# jinks_01_release.net
KiCad netlist of a schematic drawn in EAGLE
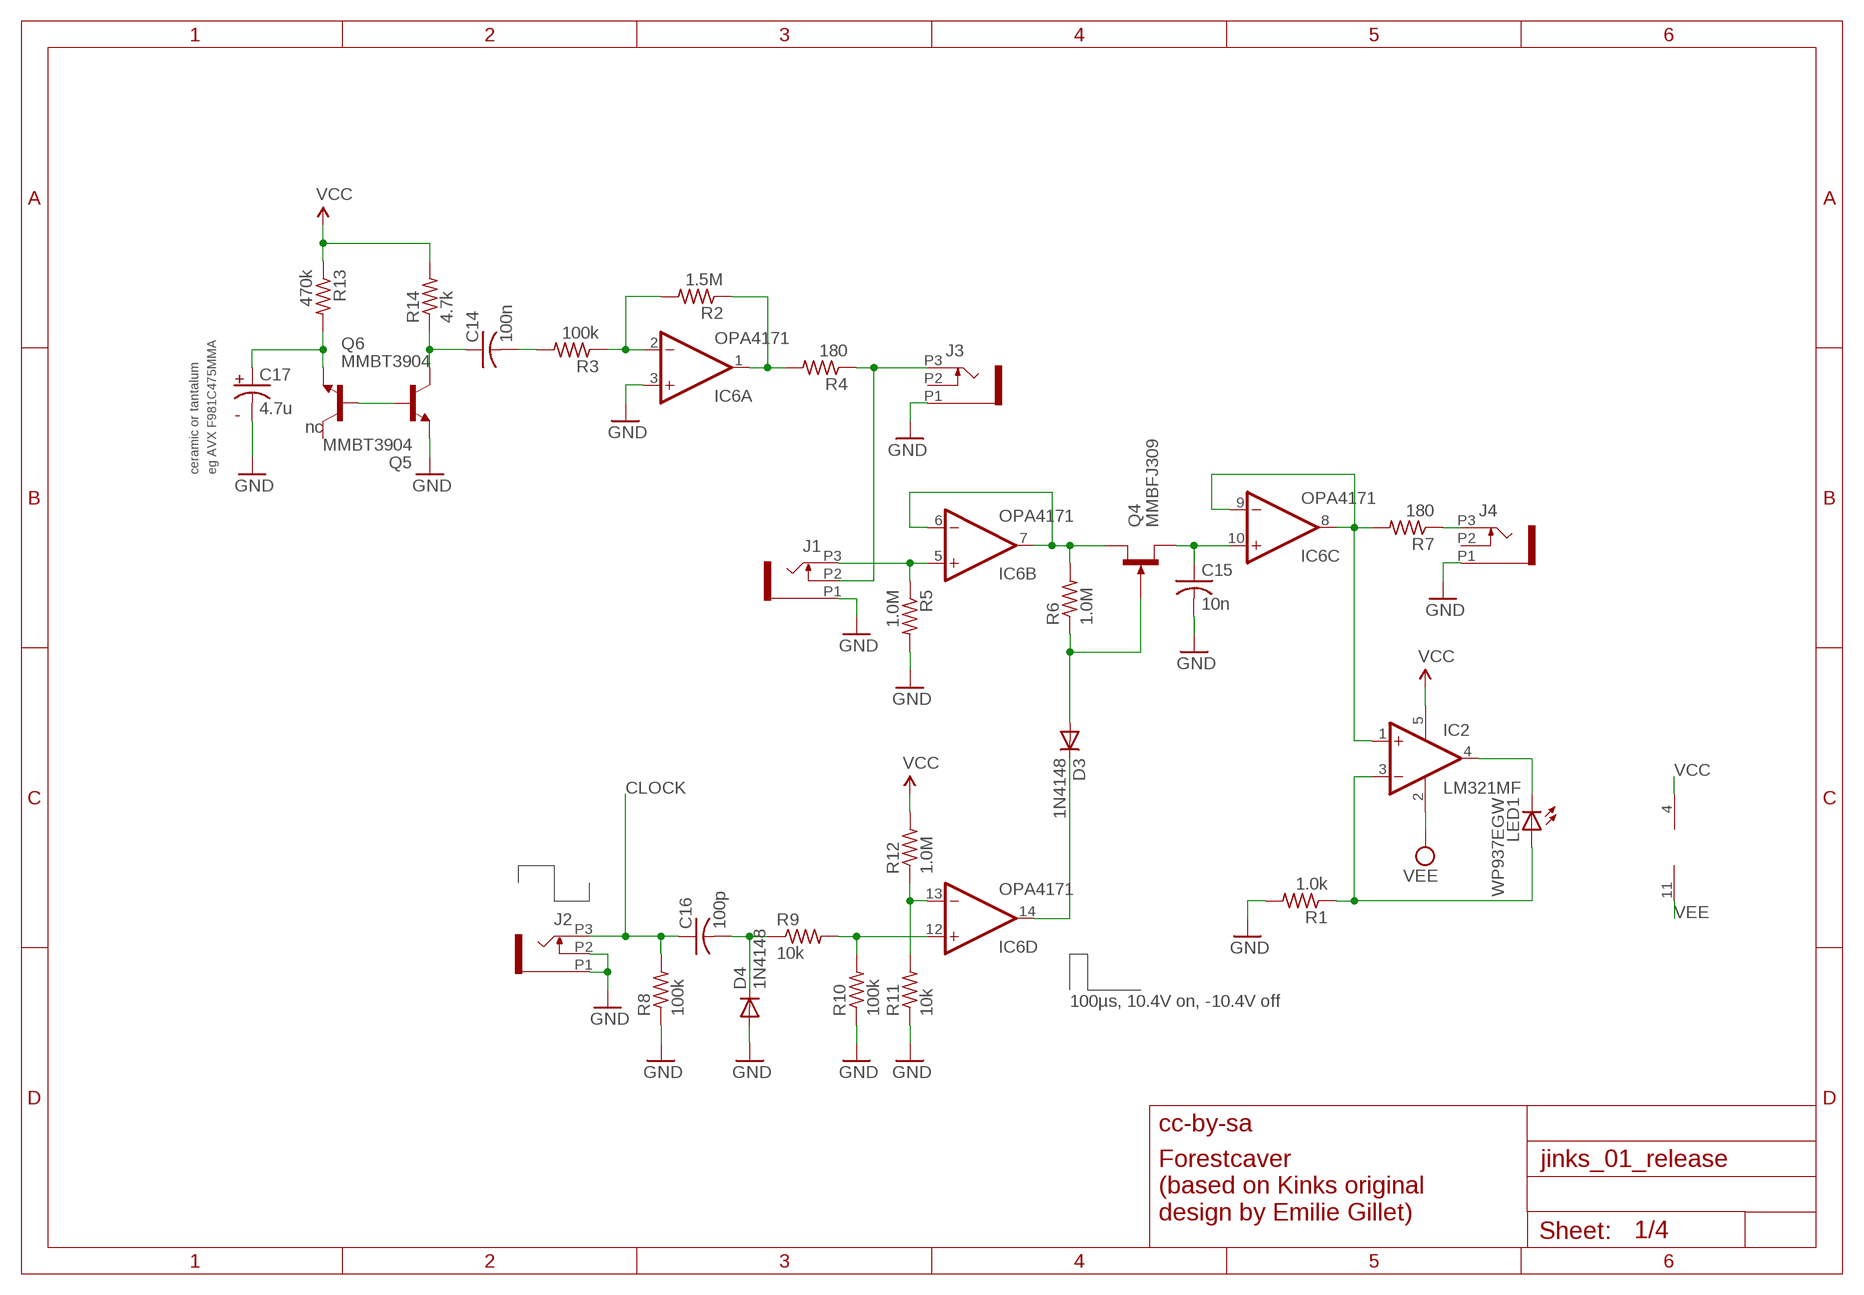
[diagram p0: schematic, sheet 1]
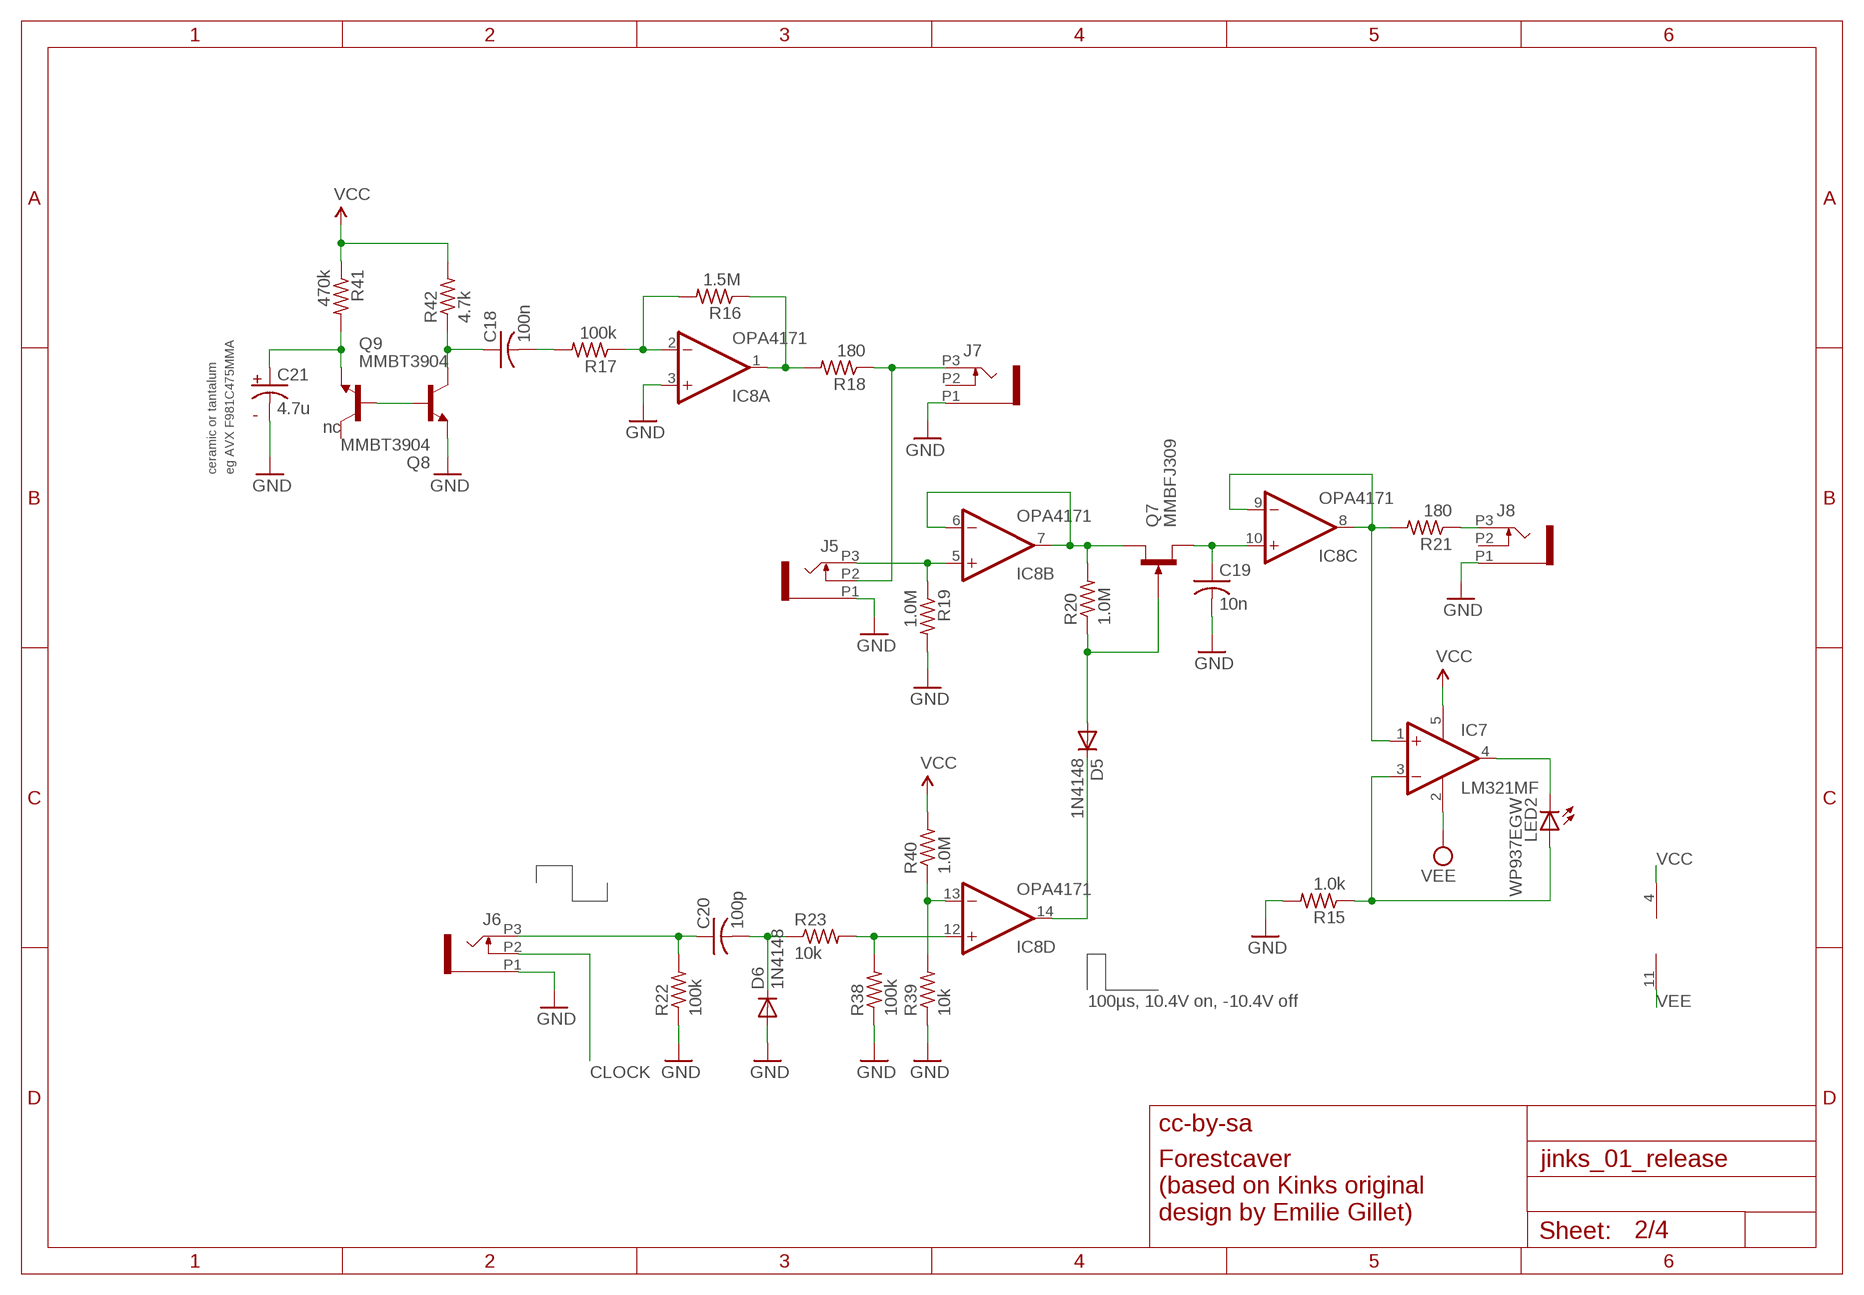
[diagram p1: schematic, sheet 2]
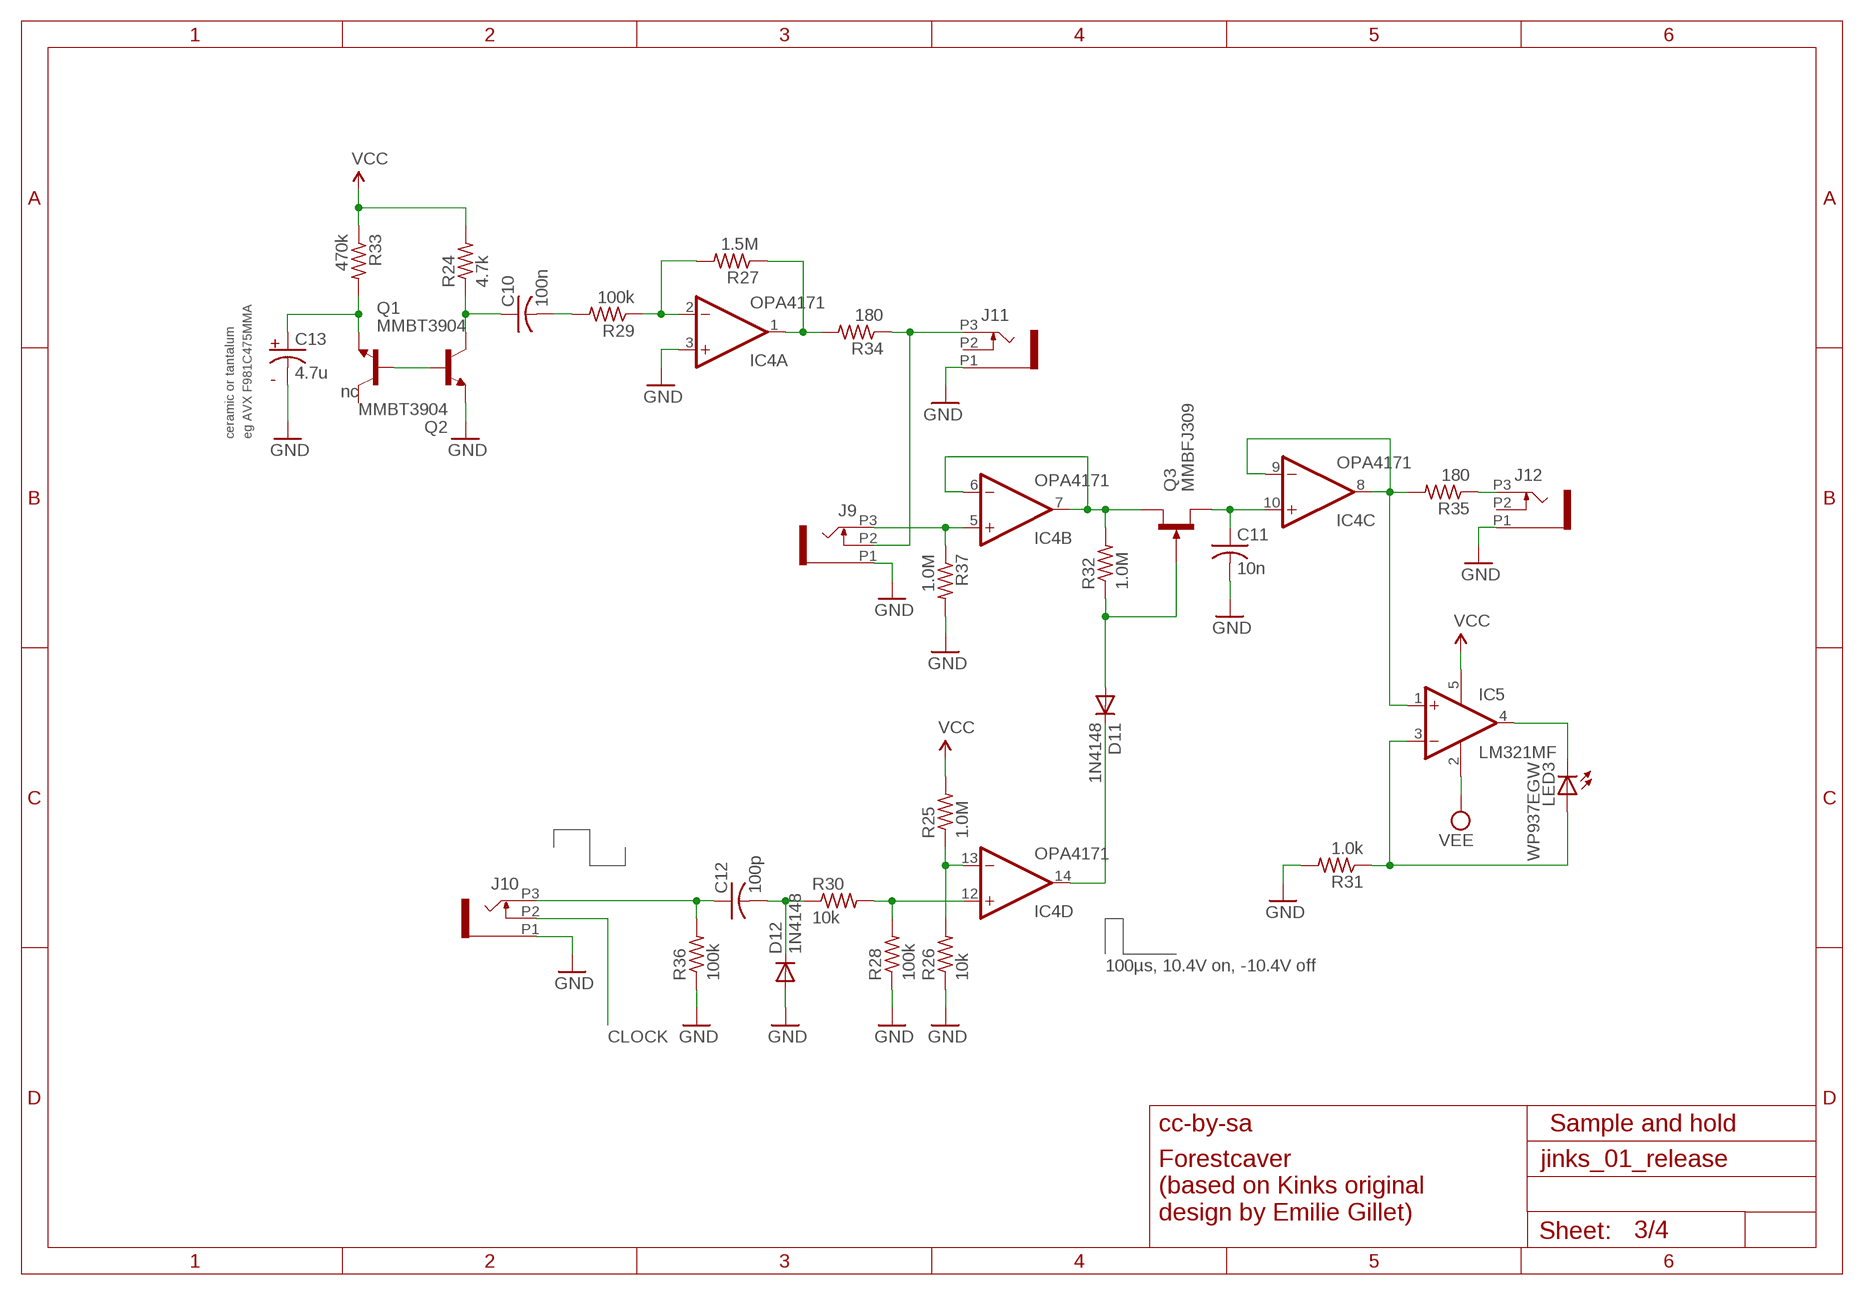
[diagram p2: schematic, sheet 3]
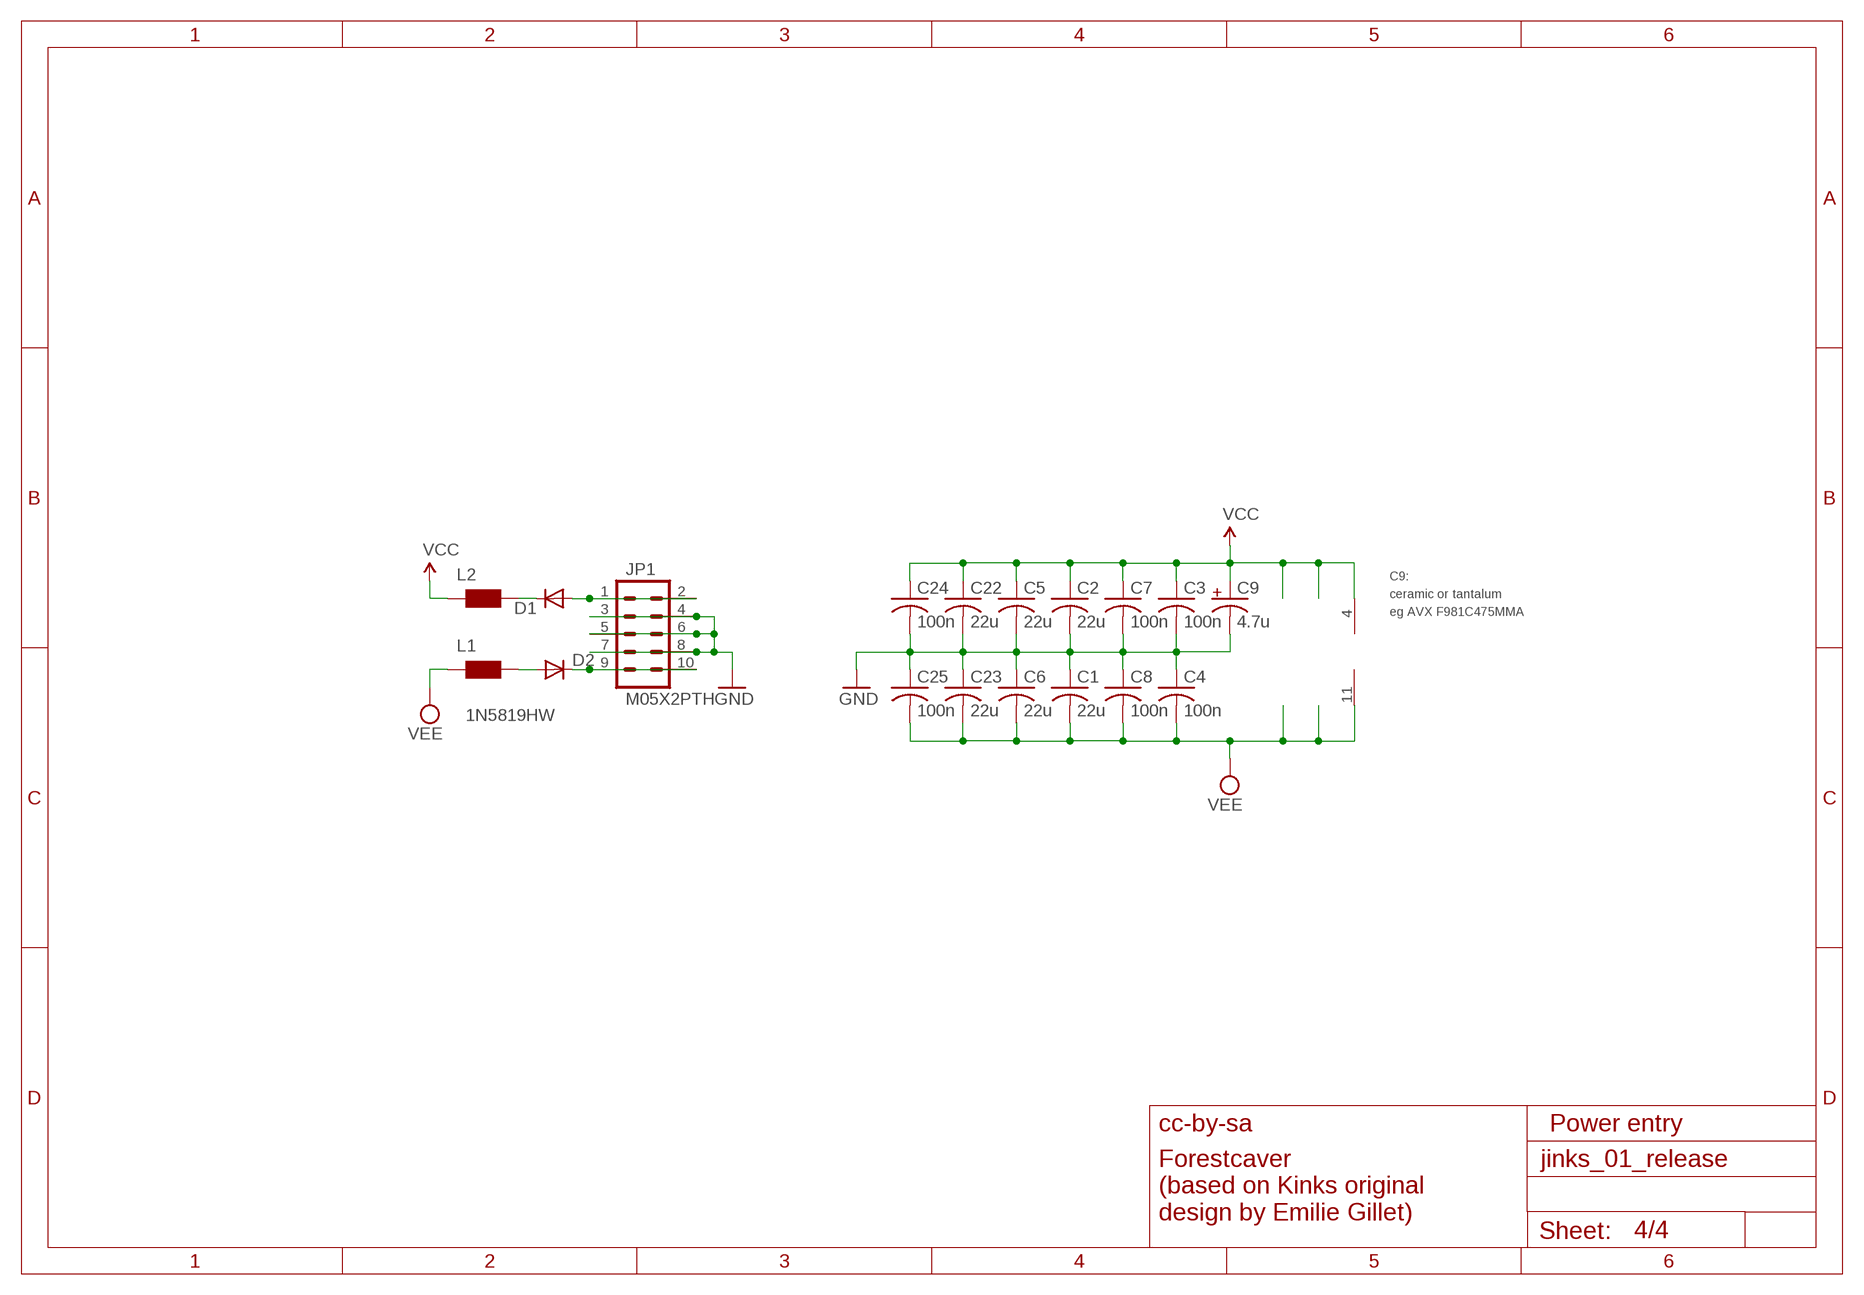
[diagram p3: schematic, sheet 4]

(export (version "E")
  (design (tool "Eeschema 10.0.6"))
  (components
    (comp (ref "C10")
      (value "100n")
      (footprint "eagle-import:C0603")
      (libsource (lib "eagle-import") (part "C-USC0603"))
    )
    (comp (ref "C11")
      (value "10n")
      (footprint "eagle-import:C0603")
      (libsource (lib "eagle-import") (part "C-USC0603"))
    )
    (comp (ref "C12")
      (value "100p")
      (footprint "eagle-import:C0603")
      (libsource (lib "eagle-import") (part "C-USC0603"))
    )
    (comp (ref "C13")
      (value "4.7u")
      (footprint "eagle-import:C0603")
      (libsource (lib "eagle-import") (part "C-USC0603"))
    )
    (comp (ref "D11")
      (value "1N4148")
      (footprint "eagle-import:SOD523")
      (libsource (lib "eagle-import") (part "DIODE-SOD523"))
    )
    (comp (ref "D12")
      (value "1N4148")
      (footprint "eagle-import:SOD523")
      (libsource (lib "eagle-import") (part "DIODE-SOD523"))
    )
    (comp (ref "IC4")
      (value "OPA4171")
      (footprint "eagle-import:TSSOP14")
      (libsource (lib "eagle-import") (part "TL074PW"))
    )
    (comp (ref "IC5")
      (value "LM321MF")
      (footprint "eagle-import:SOT23-5")
      (libsource (lib "eagle-import") (part "LM321?MF"))
    )
    (comp (ref "J9")
      (value "PJ301_THONKICONN6")
      (footprint "eagle-import:WQP_PJ_301M6")
      (libsource (lib "eagle-import") (part "PJ301_THONKICONN6"))
    )
    (comp (ref "J10")
      (value "PJ301_THONKICONN6")
      (footprint "eagle-import:WQP_PJ_301M6")
      (libsource (lib "eagle-import") (part "PJ301_THONKICONN6"))
    )
    (comp (ref "J11")
      (value "PJ301_THONKICONN6")
      (footprint "eagle-import:WQP_PJ_301M6")
      (libsource (lib "eagle-import") (part "PJ301_THONKICONN6"))
    )
    (comp (ref "J12")
      (value "PJ301_THONKICONN6")
      (footprint "eagle-import:WQP_PJ_301M6")
      (libsource (lib "eagle-import") (part "PJ301_THONKICONN6"))
    )
    (comp (ref "LED3")
      (value "WP937EGW")
      (footprint "eagle-import:LED3MM")
      (libsource (lib "eagle-import") (part "LED3MM"))
    )
    (comp (ref "Q1")
      (value "MMBT3904")
      (footprint "eagle-import:SOT23-BEC")
      (libsource (lib "eagle-import") (part "-NPN-SOT23-BECMMBT3904LT1"))
    )
    (comp (ref "Q2")
      (value "MMBT3904")
      (footprint "eagle-import:SOT23-BEC")
      (libsource (lib "eagle-import") (part "-NPN-SOT23-BECMMBT3904LT1"))
    )
    (comp (ref "Q3")
      (value "MMBFJ309")
      (footprint "eagle-import:SOT23")
      (libsource (lib "eagle-import") (part "MMBFJ3"))
    )
    (comp (ref "R24")
      (value "4.7k")
      (footprint "eagle-import:R0603")
      (libsource (lib "eagle-import") (part "R-US_R0603"))
    )
    (comp (ref "R25")
      (value "1.0M")
      (footprint "eagle-import:R0603")
      (libsource (lib "eagle-import") (part "R-US_R0603"))
    )
    (comp (ref "R26")
      (value "10k")
      (footprint "eagle-import:R0603")
      (libsource (lib "eagle-import") (part "R-US_R0603"))
    )
    (comp (ref "R27")
      (value "1.5M")
      (footprint "eagle-import:R0603")
      (libsource (lib "eagle-import") (part "R-US_R0603"))
    )
    (comp (ref "R28")
      (value "100k")
      (footprint "eagle-import:R0603")
      (libsource (lib "eagle-import") (part "R-US_R0603"))
    )
    (comp (ref "R29")
      (value "100k")
      (footprint "eagle-import:R0603")
      (libsource (lib "eagle-import") (part "R-US_R0603"))
    )
    (comp (ref "R30")
      (value "10k")
      (footprint "eagle-import:R0603")
      (libsource (lib "eagle-import") (part "R-US_R0603"))
    )
    (comp (ref "R31")
      (value "1.0k")
      (footprint "eagle-import:R0603")
      (libsource (lib "eagle-import") (part "R-US_R0603"))
    )
    (comp (ref "R32")
      (value "1.0M")
      (footprint "eagle-import:R0603")
      (libsource (lib "eagle-import") (part "R-US_R0603"))
    )
    (comp (ref "R33")
      (value "470k")
      (footprint "eagle-import:R0603")
      (libsource (lib "eagle-import") (part "R-US_R0603"))
    )
    (comp (ref "R34")
      (value "180")
      (footprint "eagle-import:R0603")
      (libsource (lib "eagle-import") (part "R-US_R0603"))
    )
    (comp (ref "R35")
      (value "180")
      (footprint "eagle-import:R0603")
      (libsource (lib "eagle-import") (part "R-US_R0603"))
    )
    (comp (ref "R36")
      (value "100k")
      (footprint "eagle-import:R0603")
      (libsource (lib "eagle-import") (part "R-US_R0603"))
    )
    (comp (ref "R37")
      (value "1.0M")
      (footprint "eagle-import:R0603")
      (libsource (lib "eagle-import") (part "R-US_R0603"))
    )
    (comp (ref "C18")
      (value "100n")
      (footprint "eagle-import:C0603")
      (libsource (lib "eagle-import") (part "C-USC0603"))
    )
    (comp (ref "C19")
      (value "10n")
      (footprint "eagle-import:C0603")
      (libsource (lib "eagle-import") (part "C-USC0603"))
    )
    (comp (ref "C20")
      (value "100p")
      (footprint "eagle-import:C0603")
      (libsource (lib "eagle-import") (part "C-USC0603"))
    )
    (comp (ref "C21")
      (value "4.7u")
      (footprint "eagle-import:C0603")
      (libsource (lib "eagle-import") (part "C-USC0603"))
    )
    (comp (ref "D5")
      (value "1N4148")
      (footprint "eagle-import:SOD523")
      (libsource (lib "eagle-import") (part "DIODE-SOD523"))
    )
    (comp (ref "D6")
      (value "1N4148")
      (footprint "eagle-import:SOD523")
      (libsource (lib "eagle-import") (part "DIODE-SOD523"))
    )
    (comp (ref "IC7")
      (value "LM321MF")
      (footprint "eagle-import:SOT23-5")
      (libsource (lib "eagle-import") (part "LM321?MF"))
    )
    (comp (ref "IC8")
      (value "OPA4171")
      (footprint "eagle-import:TSSOP14")
      (libsource (lib "eagle-import") (part "TL074PW"))
    )
    (comp (ref "J5")
      (value "PJ301_THONKICONN6")
      (footprint "eagle-import:WQP_PJ_301M6")
      (libsource (lib "eagle-import") (part "PJ301_THONKICONN6"))
    )
    (comp (ref "J6")
      (value "PJ301_THONKICONN6")
      (footprint "eagle-import:WQP_PJ_301M6")
      (libsource (lib "eagle-import") (part "PJ301_THONKICONN6"))
    )
    (comp (ref "J7")
      (value "PJ301_THONKICONN6")
      (footprint "eagle-import:WQP_PJ_301M6")
      (libsource (lib "eagle-import") (part "PJ301_THONKICONN6"))
    )
    (comp (ref "J8")
      (value "PJ301_THONKICONN6")
      (footprint "eagle-import:WQP_PJ_301M6")
      (libsource (lib "eagle-import") (part "PJ301_THONKICONN6"))
    )
    (comp (ref "LED2")
      (value "WP937EGW")
      (footprint "eagle-import:LED3MM")
      (libsource (lib "eagle-import") (part "LED3MM"))
    )
    (comp (ref "Q7")
      (value "MMBFJ309")
      (footprint "eagle-import:SOT23")
      (libsource (lib "eagle-import") (part "MMBFJ3"))
    )
    (comp (ref "Q8")
      (value "MMBT3904")
      (footprint "eagle-import:SOT23-BEC")
      (libsource (lib "eagle-import") (part "-NPN-SOT23-BECMMBT3904LT1"))
    )
    (comp (ref "Q9")
      (value "MMBT3904")
      (footprint "eagle-import:SOT23-BEC")
      (libsource (lib "eagle-import") (part "-NPN-SOT23-BECMMBT3904LT1"))
    )
    (comp (ref "R15")
      (value "1.0k")
      (footprint "eagle-import:R0603")
      (libsource (lib "eagle-import") (part "R-US_R0603"))
    )
    (comp (ref "R16")
      (value "1.5M")
      (footprint "eagle-import:R0603")
      (libsource (lib "eagle-import") (part "R-US_R0603"))
    )
    (comp (ref "R17")
      (value "100k")
      (footprint "eagle-import:R0603")
      (libsource (lib "eagle-import") (part "R-US_R0603"))
    )
    (comp (ref "R18")
      (value "180")
      (footprint "eagle-import:R0603")
      (libsource (lib "eagle-import") (part "R-US_R0603"))
    )
    (comp (ref "R19")
      (value "1.0M")
      (footprint "eagle-import:R0603")
      (libsource (lib "eagle-import") (part "R-US_R0603"))
    )
    (comp (ref "R20")
      (value "1.0M")
      (footprint "eagle-import:R0603")
      (libsource (lib "eagle-import") (part "R-US_R0603"))
    )
    (comp (ref "R21")
      (value "180")
      (footprint "eagle-import:R0603")
      (libsource (lib "eagle-import") (part "R-US_R0603"))
    )
    (comp (ref "R22")
      (value "100k")
      (footprint "eagle-import:R0603")
      (libsource (lib "eagle-import") (part "R-US_R0603"))
    )
    (comp (ref "R23")
      (value "10k")
      (footprint "eagle-import:R0603")
      (libsource (lib "eagle-import") (part "R-US_R0603"))
    )
    (comp (ref "R38")
      (value "100k")
      (footprint "eagle-import:R0603")
      (libsource (lib "eagle-import") (part "R-US_R0603"))
    )
    (comp (ref "R39")
      (value "10k")
      (footprint "eagle-import:R0603")
      (libsource (lib "eagle-import") (part "R-US_R0603"))
    )
    (comp (ref "R40")
      (value "1.0M")
      (footprint "eagle-import:R0603")
      (libsource (lib "eagle-import") (part "R-US_R0603"))
    )
    (comp (ref "R41")
      (value "470k")
      (footprint "eagle-import:R0603")
      (libsource (lib "eagle-import") (part "R-US_R0603"))
    )
    (comp (ref "R42")
      (value "4.7k")
      (footprint "eagle-import:R0603")
      (libsource (lib "eagle-import") (part "R-US_R0603"))
    )
    (comp (ref "C14")
      (value "100n")
      (footprint "eagle-import:C0603")
      (libsource (lib "eagle-import") (part "C-USC0603"))
    )
    (comp (ref "C15")
      (value "10n")
      (footprint "eagle-import:C0603")
      (libsource (lib "eagle-import") (part "C-USC0603"))
    )
    (comp (ref "C16")
      (value "100p")
      (footprint "eagle-import:C0603")
      (libsource (lib "eagle-import") (part "C-USC0603"))
    )
    (comp (ref "C17")
      (value "4.7u")
      (footprint "eagle-import:C0603")
      (libsource (lib "eagle-import") (part "C-USC0603"))
    )
    (comp (ref "D3")
      (value "1N4148")
      (footprint "eagle-import:SOD523")
      (libsource (lib "eagle-import") (part "DIODE-SOD523"))
    )
    (comp (ref "D4")
      (value "1N4148")
      (footprint "eagle-import:SOD523")
      (libsource (lib "eagle-import") (part "DIODE-SOD523"))
    )
    (comp (ref "IC2")
      (value "LM321MF")
      (footprint "eagle-import:SOT23-5")
      (libsource (lib "eagle-import") (part "LM321?MF"))
    )
    (comp (ref "IC6")
      (value "OPA4171")
      (footprint "eagle-import:TSSOP14")
      (libsource (lib "eagle-import") (part "TL074PW"))
    )
    (comp (ref "J1")
      (value "PJ301_THONKICONN6")
      (footprint "eagle-import:WQP_PJ_301M6")
      (libsource (lib "eagle-import") (part "PJ301_THONKICONN6"))
    )
    (comp (ref "J2")
      (value "PJ301_THONKICONN6")
      (footprint "eagle-import:WQP_PJ_301M6")
      (libsource (lib "eagle-import") (part "PJ301_THONKICONN6"))
    )
    (comp (ref "J3")
      (value "PJ301_THONKICONN6")
      (footprint "eagle-import:WQP_PJ_301M6")
      (libsource (lib "eagle-import") (part "PJ301_THONKICONN6"))
    )
    (comp (ref "J4")
      (value "PJ301_THONKICONN6")
      (footprint "eagle-import:WQP_PJ_301M6")
      (libsource (lib "eagle-import") (part "PJ301_THONKICONN6"))
    )
    (comp (ref "LED1")
      (value "WP937EGW")
      (footprint "eagle-import:LED3MM")
      (libsource (lib "eagle-import") (part "LED3MM"))
    )
    (comp (ref "Q4")
      (value "MMBFJ309")
      (footprint "eagle-import:SOT23")
      (libsource (lib "eagle-import") (part "MMBFJ3"))
    )
    (comp (ref "Q5")
      (value "MMBT3904")
      (footprint "eagle-import:SOT23-BEC")
      (libsource (lib "eagle-import") (part "-NPN-SOT23-BECMMBT3904LT1"))
    )
    (comp (ref "Q6")
      (value "MMBT3904")
      (footprint "eagle-import:SOT23-BEC")
      (libsource (lib "eagle-import") (part "-NPN-SOT23-BECMMBT3904LT1"))
    )
    (comp (ref "R1")
      (value "1.0k")
      (footprint "eagle-import:R0603")
      (libsource (lib "eagle-import") (part "R-US_R0603"))
    )
    (comp (ref "R2")
      (value "1.5M")
      (footprint "eagle-import:R0603")
      (libsource (lib "eagle-import") (part "R-US_R0603"))
    )
    (comp (ref "R3")
      (value "100k")
      (footprint "eagle-import:R0603")
      (libsource (lib "eagle-import") (part "R-US_R0603"))
    )
    (comp (ref "R4")
      (value "180")
      (footprint "eagle-import:R0603")
      (libsource (lib "eagle-import") (part "R-US_R0603"))
    )
    (comp (ref "R5")
      (value "1.0M")
      (footprint "eagle-import:R0603")
      (libsource (lib "eagle-import") (part "R-US_R0603"))
    )
    (comp (ref "R6")
      (value "1.0M")
      (footprint "eagle-import:R0603")
      (libsource (lib "eagle-import") (part "R-US_R0603"))
    )
    (comp (ref "R7")
      (value "180")
      (footprint "eagle-import:R0603")
      (libsource (lib "eagle-import") (part "R-US_R0603"))
    )
    (comp (ref "R8")
      (value "100k")
      (footprint "eagle-import:R0603")
      (libsource (lib "eagle-import") (part "R-US_R0603"))
    )
    (comp (ref "R9")
      (value "10k")
      (footprint "eagle-import:R0603")
      (libsource (lib "eagle-import") (part "R-US_R0603"))
    )
    (comp (ref "R10")
      (value "100k")
      (footprint "eagle-import:R0603")
      (libsource (lib "eagle-import") (part "R-US_R0603"))
    )
    (comp (ref "R11")
      (value "10k")
      (footprint "eagle-import:R0603")
      (libsource (lib "eagle-import") (part "R-US_R0603"))
    )
    (comp (ref "R12")
      (value "1.0M")
      (footprint "eagle-import:R0603")
      (libsource (lib "eagle-import") (part "R-US_R0603"))
    )
    (comp (ref "R13")
      (value "470k")
      (footprint "eagle-import:R0603")
      (libsource (lib "eagle-import") (part "R-US_R0603"))
    )
    (comp (ref "R14")
      (value "4.7k")
      (footprint "eagle-import:R0603")
      (libsource (lib "eagle-import") (part "R-US_R0603"))
    )
    (comp (ref "C1")
      (value "22u")
      (footprint "eagle-import:C0805")
      (libsource (lib "eagle-import") (part "C-USC0805"))
    )
    (comp (ref "C2")
      (value "22u")
      (footprint "eagle-import:C0805")
      (libsource (lib "eagle-import") (part "C-USC0805"))
    )
    (comp (ref "C3")
      (value "100n")
      (footprint "eagle-import:C0603")
      (libsource (lib "eagle-import") (part "C-USC0603"))
    )
    (comp (ref "C4")
      (value "100n")
      (footprint "eagle-import:C0603")
      (libsource (lib "eagle-import") (part "C-USC0603"))
    )
    (comp (ref "C5")
      (value "22u")
      (footprint "eagle-import:C0805")
      (libsource (lib "eagle-import") (part "C-USC0805"))
    )
    (comp (ref "C6")
      (value "22u")
      (footprint "eagle-import:C0805")
      (libsource (lib "eagle-import") (part "C-USC0805"))
    )
    (comp (ref "C7")
      (value "100n")
      (footprint "eagle-import:C0603")
      (libsource (lib "eagle-import") (part "C-USC0603"))
    )
    (comp (ref "C8")
      (value "100n")
      (footprint "eagle-import:C0603")
      (libsource (lib "eagle-import") (part "C-USC0603"))
    )
    (comp (ref "C9")
      (value "4.7u")
      (footprint "eagle-import:C0603")
      (libsource (lib "eagle-import") (part "C-USC0603"))
    )
    (comp (ref "C22")
      (value "22u")
      (footprint "eagle-import:C0805")
      (libsource (lib "eagle-import") (part "C-USC0805"))
    )
    (comp (ref "C23")
      (value "22u")
      (footprint "eagle-import:C0805")
      (libsource (lib "eagle-import") (part "C-USC0805"))
    )
    (comp (ref "C24")
      (value "100n")
      (footprint "eagle-import:C0603")
      (libsource (lib "eagle-import") (part "C-USC0603"))
    )
    (comp (ref "C25")
      (value "100n")
      (footprint "eagle-import:C0603")
      (libsource (lib "eagle-import") (part "C-USC0603"))
    )
    (comp (ref "D1")
      (value "1N5819HW")
      (footprint "eagle-import:SOD123")
      (libsource (lib "eagle-import") (part "DIODE-SOD123"))
    )
    (comp (ref "D2")
      (value "1N5819HW")
      (footprint "eagle-import:SOD123")
      (libsource (lib "eagle-import") (part "DIODE-SOD123"))
    )
    (comp (ref "JP1")
      (value "M05X2PTH")
      (footprint "eagle-import:AVR_ICSP")
      (libsource (lib "eagle-import") (part "M05X2PTH"))
    )
    (comp (ref "L1")
      (value "WE-CBF_0603")
      (footprint "eagle-import:0603")
      (libsource (lib "eagle-import") (part "WE-CBF_0603"))
    )
    (comp (ref "L2")
      (value "WE-CBF_0603")
      (footprint "eagle-import:0603")
      (libsource (lib "eagle-import") (part "WE-CBF_0603"))
    )
  )
  (nets
    (net (code "1") (name "CLOCK") (class "Default")
      (node (ref "C16") (pin "1") (pinfunction "1_1") (pintype "passive"))
      (node (ref "J10") (pin "P2") (pinfunction "2_P2") (pintype "passive"))
      (node (ref "J2") (pin "P3") (pinfunction "3_P3") (pintype "passive"))
      (node (ref "J6") (pin "P2") (pinfunction "2_P2") (pintype "passive"))
      (node (ref "R8") (pin "2") (pinfunction "2_2") (pintype "passive"))
    )
    (net (code "2") (name "GND") (class "Default")
      (node (ref "C1") (pin "1") (pinfunction "1_1") (pintype "passive"))
      (node (ref "C11") (pin "2") (pinfunction "2_2") (pintype "passive"))
      (node (ref "C13") (pin "2") (pinfunction "2_2") (pintype "passive"))
      (node (ref "C15") (pin "2") (pinfunction "2_2") (pintype "passive"))
      (node (ref "C17") (pin "2") (pinfunction "2_2") (pintype "passive"))
      (node (ref "C19") (pin "2") (pinfunction "2_2") (pintype "passive"))
      (node (ref "C2") (pin "2") (pinfunction "2_2") (pintype "passive"))
      (node (ref "C21") (pin "2") (pinfunction "2_2") (pintype "passive"))
      (node (ref "C22") (pin "2") (pinfunction "2_2") (pintype "passive"))
      (node (ref "C23") (pin "1") (pinfunction "1_1") (pintype "passive"))
      (node (ref "C24") (pin "2") (pinfunction "2_2") (pintype "passive"))
      (node (ref "C25") (pin "1") (pinfunction "1_1") (pintype "passive"))
      (node (ref "C3") (pin "2") (pinfunction "2_2") (pintype "passive"))
      (node (ref "C4") (pin "1") (pinfunction "1_1") (pintype "passive"))
      (node (ref "C5") (pin "2") (pinfunction "2_2") (pintype "passive"))
      (node (ref "C6") (pin "1") (pinfunction "1_1") (pintype "passive"))
      (node (ref "C7") (pin "2") (pinfunction "2_2") (pintype "passive"))
      (node (ref "C8") (pin "1") (pinfunction "1_1") (pintype "passive"))
      (node (ref "C9") (pin "2") (pinfunction "2_2") (pintype "passive"))
      (node (ref "D12") (pin "A") (pinfunction "A_A") (pintype "passive"))
      (node (ref "D4") (pin "A") (pinfunction "A_A") (pintype "passive"))
      (node (ref "D6") (pin "A") (pinfunction "A_A") (pintype "passive"))
      (node (ref "IC4") (pin "3") (pinfunction "+IN_3") (pintype "input"))
      (node (ref "IC6") (pin "3") (pinfunction "+IN_3") (pintype "input"))
      (node (ref "IC8") (pin "3") (pinfunction "+IN_3") (pintype "input"))
      (node (ref "J1") (pin "P1") (pinfunction "1_P1") (pintype "passive"))
      (node (ref "J10") (pin "P1") (pinfunction "1_P1") (pintype "passive"))
      (node (ref "J11") (pin "P1") (pinfunction "1_P1") (pintype "passive"))
      (node (ref "J12") (pin "P1") (pinfunction "1_P1") (pintype "passive"))
      (node (ref "J2") (pin "P1") (pinfunction "1_P1") (pintype "passive"))
      (node (ref "J2") (pin "P2") (pinfunction "2_P2") (pintype "passive"))
      (node (ref "J3") (pin "P1") (pinfunction "1_P1") (pintype "passive"))
      (node (ref "J4") (pin "P1") (pinfunction "1_P1") (pintype "passive"))
      (node (ref "J5") (pin "P1") (pinfunction "1_P1") (pintype "passive"))
      (node (ref "J6") (pin "P1") (pinfunction "1_P1") (pintype "passive"))
      (node (ref "J7") (pin "P1") (pinfunction "1_P1") (pintype "passive"))
      (node (ref "J8") (pin "P1") (pinfunction "1_P1") (pintype "passive"))
      (node (ref "J9") (pin "P1") (pinfunction "1_P1") (pintype "passive"))
      (node (ref "JP1") (pin "3") (pinfunction "3_3") (pintype "passive"))
      (node (ref "JP1") (pin "4") (pinfunction "4_4") (pintype "passive"))
      (node (ref "JP1") (pin "5") (pinfunction "5_5") (pintype "passive"))
      (node (ref "JP1") (pin "6") (pinfunction "6_6") (pintype "passive"))
      (node (ref "JP1") (pin "7") (pinfunction "7_7") (pintype "passive"))
      (node (ref "JP1") (pin "8") (pinfunction "8_8") (pintype "passive"))
      (node (ref "Q1") (pin "E") (pinfunction "E_E") (pintype "passive"))
      (node (ref "Q6") (pin "E") (pinfunction "E_E") (pintype "passive"))
      (node (ref "Q9") (pin "E") (pinfunction "E_E") (pintype "passive"))
      (node (ref "R1") (pin "2") (pinfunction "2_2") (pintype "passive"))
      (node (ref "R10") (pin "1") (pinfunction "1_1") (pintype "passive"))
      (node (ref "R11") (pin "1") (pinfunction "1_1") (pintype "passive"))
      (node (ref "R15") (pin "2") (pinfunction "2_2") (pintype "passive"))
      (node (ref "R19") (pin "2") (pinfunction "2_2") (pintype "passive"))
      (node (ref "R22") (pin "1") (pinfunction "1_1") (pintype "passive"))
      (node (ref "R26") (pin "1") (pinfunction "1_1") (pintype "passive"))
      (node (ref "R28") (pin "1") (pinfunction "1_1") (pintype "passive"))
      (node (ref "R31") (pin "2") (pinfunction "2_2") (pintype "passive"))
      (node (ref "R36") (pin "1") (pinfunction "1_1") (pintype "passive"))
      (node (ref "R37") (pin "2") (pinfunction "2_2") (pintype "passive"))
      (node (ref "R38") (pin "1") (pinfunction "1_1") (pintype "passive"))
      (node (ref "R39") (pin "1") (pinfunction "1_1") (pintype "passive"))
      (node (ref "R5") (pin "2") (pinfunction "2_2") (pintype "passive"))
      (node (ref "R8") (pin "1") (pinfunction "1_1") (pintype "passive"))
    )
    (net (code "3") (name "Net-(C10-Pad1)") (class "Default")
      (node (ref "C10") (pin "1") (pinfunction "1_1") (pintype "passive"))
      (node (ref "Q1") (pin "C") (pinfunction "C_C") (pintype "passive"))
      (node (ref "R24") (pin "1") (pinfunction "1_1") (pintype "passive"))
    )
    (net (code "4") (name "Net-(C10-Pad2)") (class "Default")
      (node (ref "C10") (pin "2") (pinfunction "2_2") (pintype "passive"))
      (node (ref "R29") (pin "2") (pinfunction "2_2") (pintype "passive"))
    )
    (net (code "5") (name "Net-(C12-Pad2)") (class "Default")
      (node (ref "C12") (pin "2") (pinfunction "2_2") (pintype "passive"))
      (node (ref "D12") (pin "C") (pinfunction "C_C") (pintype "passive"))
      (node (ref "R30") (pin "1") (pinfunction "1_1") (pintype "passive"))
    )
    (net (code "6") (name "Net-(C13-Pad1)") (class "Default")
      (node (ref "C13") (pin "1") (pinfunction "1_1") (pintype "passive"))
      (node (ref "Q2") (pin "E") (pinfunction "E_E") (pintype "passive"))
      (node (ref "R33") (pin "2") (pinfunction "2_2") (pintype "passive"))
    )
    (net (code "7") (name "Net-(C14-Pad1)") (class "Default")
      (node (ref "C14") (pin "1") (pinfunction "1_1") (pintype "passive"))
      (node (ref "Q6") (pin "C") (pinfunction "C_C") (pintype "passive"))
      (node (ref "R14") (pin "1") (pinfunction "1_1") (pintype "passive"))
    )
    (net (code "8") (name "Net-(C14-Pad2)") (class "Default")
      (node (ref "C14") (pin "2") (pinfunction "2_2") (pintype "passive"))
      (node (ref "R3") (pin "2") (pinfunction "2_2") (pintype "passive"))
    )
    (net (code "9") (name "Net-(C16-Pad2)") (class "Default")
      (node (ref "C16") (pin "2") (pinfunction "2_2") (pintype "passive"))
      (node (ref "D4") (pin "C") (pinfunction "C_C") (pintype "passive"))
      (node (ref "R9") (pin "1") (pinfunction "1_1") (pintype "passive"))
    )
    (net (code "10") (name "Net-(C17-Pad1)") (class "Default")
      (node (ref "C17") (pin "1") (pinfunction "1_1") (pintype "passive"))
      (node (ref "Q5") (pin "E") (pinfunction "E_E") (pintype "passive"))
      (node (ref "R13") (pin "2") (pinfunction "2_2") (pintype "passive"))
    )
    (net (code "11") (name "Net-(C18-Pad1)") (class "Default")
      (node (ref "C18") (pin "1") (pinfunction "1_1") (pintype "passive"))
      (node (ref "Q9") (pin "C") (pinfunction "C_C") (pintype "passive"))
      (node (ref "R42") (pin "1") (pinfunction "1_1") (pintype "passive"))
    )
    (net (code "12") (name "Net-(C18-Pad2)") (class "Default")
      (node (ref "C18") (pin "2") (pinfunction "2_2") (pintype "passive"))
      (node (ref "R17") (pin "2") (pinfunction "2_2") (pintype "passive"))
    )
    (net (code "13") (name "Net-(C20-Pad2)") (class "Default")
      (node (ref "C20") (pin "2") (pinfunction "2_2") (pintype "passive"))
      (node (ref "D6") (pin "C") (pinfunction "C_C") (pintype "passive"))
      (node (ref "R23") (pin "1") (pinfunction "1_1") (pintype "passive"))
    )
    (net (code "14") (name "Net-(C21-Pad1)") (class "Default")
      (node (ref "C21") (pin "1") (pinfunction "1_1") (pintype "passive"))
      (node (ref "Q8") (pin "E") (pinfunction "E_E") (pintype "passive"))
      (node (ref "R41") (pin "2") (pinfunction "2_2") (pintype "passive"))
    )
    (net (code "15") (name "Net-(D1-PadA)") (class "Default")
      (node (ref "D1") (pin "A") (pinfunction "A_A") (pintype "passive"))
      (node (ref "JP1") (pin "1") (pinfunction "1_1") (pintype "passive"))
      (node (ref "JP1") (pin "2") (pinfunction "2_2") (pintype "passive"))
    )
    (net (code "16") (name "Net-(D1-PadC)") (class "Default")
      (node (ref "D1") (pin "C") (pinfunction "C_C") (pintype "passive"))
      (node (ref "L2") (pin "2") (pinfunction "2_2") (pintype "passive"))
    )
    (net (code "17") (name "Net-(D2-PadA)") (class "Default")
      (node (ref "D2") (pin "A") (pinfunction "A_A") (pintype "passive"))
      (node (ref "L1") (pin "2") (pinfunction "2_2") (pintype "passive"))
    )
    (net (code "18") (name "Net-(D2-PadC)") (class "Default")
      (node (ref "D2") (pin "C") (pinfunction "C_C") (pintype "passive"))
      (node (ref "JP1") (pin "10") (pinfunction "10_10") (pintype "passive"))
      (node (ref "JP1") (pin "9") (pinfunction "9_9") (pintype "passive"))
    )
    (net (code "19") (name "Net-(IC2-+IN)") (class "Default")
      (node (ref "IC2") (pin "1") (pinfunction "+IN_1") (pintype "input"))
      (node (ref "IC6") (pin "8") (pinfunction "OUT_8") (pintype "output"))
      (node (ref "IC6") (pin "9") (pinfunction "-IN_9") (pintype "input"))
      (node (ref "R7") (pin "2") (pinfunction "2_2") (pintype "passive"))
    )
    (net (code "20") (name "Net-(IC2--IN)") (class "Default")
      (node (ref "IC2") (pin "3") (pinfunction "-IN_3") (pintype "input"))
      (node (ref "LED1") (pin "A") (pinfunction "A_A") (pintype "passive"))
      (node (ref "R1") (pin "1") (pinfunction "1_1") (pintype "passive"))
    )
    (net (code "21") (name "Net-(IC2-OUT)") (class "Default")
      (node (ref "IC2") (pin "4") (pinfunction "OUT_4") (pintype "output"))
      (node (ref "LED1") (pin "K") (pinfunction "C_K") (pintype "passive"))
    )
    (net (code "22") (name "Net-(IC4A--IN)") (class "Default")
      (node (ref "IC4") (pin "2") (pinfunction "-IN_2") (pintype "input"))
      (node (ref "R27") (pin "2") (pinfunction "2_2") (pintype "passive"))
      (node (ref "R29") (pin "1") (pinfunction "1_1") (pintype "passive"))
    )
    (net (code "23") (name "Net-(IC4A-OUT)") (class "Default")
      (node (ref "IC4") (pin "1") (pinfunction "OUT_1") (pintype "output"))
      (node (ref "R27") (pin "1") (pinfunction "1_1") (pintype "passive"))
      (node (ref "R34") (pin "2") (pinfunction "2_2") (pintype "passive"))
    )
    (net (code "24") (name "Net-(IC4B-+IN)") (class "Default")
      (node (ref "IC4") (pin "5") (pinfunction "+IN_5") (pintype "input"))
      (node (ref "J9") (pin "P3") (pinfunction "3_P3") (pintype "passive"))
      (node (ref "R37") (pin "1") (pinfunction "1_1") (pintype "passive"))
    )
    (net (code "25") (name "Net-(IC4B--IN)") (class "Default")
      (node (ref "IC4") (pin "6") (pinfunction "-IN_6") (pintype "input"))
      (node (ref "IC4") (pin "7") (pinfunction "OUT_7") (pintype "output"))
      (node (ref "Q3") (pin "1") (pinfunction "D_1") (pintype "passive"))
      (node (ref "R32") (pin "2") (pinfunction "2_2") (pintype "passive"))
    )
    (net (code "26") (name "Net-(IC4C-+IN)") (class "Default")
      (node (ref "C11") (pin "1") (pinfunction "1_1") (pintype "passive"))
      (node (ref "IC4") (pin "10") (pinfunction "+IN_10") (pintype "input"))
      (node (ref "Q3") (pin "2") (pinfunction "S_2") (pintype "passive"))
    )
    (net (code "27") (name "Net-(IC4C--IN)") (class "Default")
      (node (ref "IC4") (pin "8") (pinfunction "OUT_8") (pintype "output"))
      (node (ref "IC4") (pin "9") (pinfunction "-IN_9") (pintype "input"))
      (node (ref "IC5") (pin "1") (pinfunction "+IN_1") (pintype "input"))
      (node (ref "R35") (pin "2") (pinfunction "2_2") (pintype "passive"))
    )
    (net (code "28") (name "Net-(IC4D-+IN)") (class "Default")
      (node (ref "IC4") (pin "12") (pinfunction "+IN_12") (pintype "input"))
      (node (ref "R28") (pin "2") (pinfunction "2_2") (pintype "passive"))
      (node (ref "R30") (pin "2") (pinfunction "2_2") (pintype "passive"))
    )
    (net (code "29") (name "Net-(IC4D--IN)") (class "Default")
      (node (ref "IC4") (pin "13") (pinfunction "-IN_13") (pintype "input"))
      (node (ref "R25") (pin "1") (pinfunction "1_1") (pintype "passive"))
      (node (ref "R26") (pin "2") (pinfunction "2_2") (pintype "passive"))
    )
    (net (code "30") (name "Net-(IC4D-OUT)") (class "Default")
      (node (ref "D11") (pin "C") (pinfunction "C_C") (pintype "passive"))
      (node (ref "IC4") (pin "14") (pinfunction "OUT_14") (pintype "output"))
    )
    (net (code "31") (name "Net-(IC5--IN)") (class "Default")
      (node (ref "IC5") (pin "3") (pinfunction "-IN_3") (pintype "input"))
      (node (ref "LED3") (pin "A") (pinfunction "A_A") (pintype "passive"))
      (node (ref "R31") (pin "1") (pinfunction "1_1") (pintype "passive"))
    )
    (net (code "32") (name "Net-(IC5-OUT)") (class "Default")
      (node (ref "IC5") (pin "4") (pinfunction "OUT_4") (pintype "output"))
      (node (ref "LED3") (pin "K") (pinfunction "C_K") (pintype "passive"))
    )
    (net (code "33") (name "Net-(IC6A--IN)") (class "Default")
      (node (ref "IC6") (pin "2") (pinfunction "-IN_2") (pintype "input"))
      (node (ref "R2") (pin "2") (pinfunction "2_2") (pintype "passive"))
      (node (ref "R3") (pin "1") (pinfunction "1_1") (pintype "passive"))
    )
    (net (code "34") (name "Net-(IC6A-OUT)") (class "Default")
      (node (ref "IC6") (pin "1") (pinfunction "OUT_1") (pintype "output"))
      (node (ref "R2") (pin "1") (pinfunction "1_1") (pintype "passive"))
      (node (ref "R4") (pin "2") (pinfunction "2_2") (pintype "passive"))
    )
    (net (code "35") (name "Net-(IC6B-+IN)") (class "Default")
      (node (ref "IC6") (pin "5") (pinfunction "+IN_5") (pintype "input"))
      (node (ref "J1") (pin "P3") (pinfunction "3_P3") (pintype "passive"))
      (node (ref "R5") (pin "1") (pinfunction "1_1") (pintype "passive"))
    )
    (net (code "36") (name "Net-(IC6B--IN)") (class "Default")
      (node (ref "IC6") (pin "6") (pinfunction "-IN_6") (pintype "input"))
      (node (ref "IC6") (pin "7") (pinfunction "OUT_7") (pintype "output"))
      (node (ref "Q4") (pin "1") (pinfunction "D_1") (pintype "passive"))
      (node (ref "R6") (pin "2") (pinfunction "2_2") (pintype "passive"))
    )
    (net (code "37") (name "Net-(IC6C-+IN)") (class "Default")
      (node (ref "C15") (pin "1") (pinfunction "1_1") (pintype "passive"))
      (node (ref "IC6") (pin "10") (pinfunction "+IN_10") (pintype "input"))
      (node (ref "Q4") (pin "2") (pinfunction "S_2") (pintype "passive"))
    )
    (net (code "38") (name "Net-(IC6D-+IN)") (class "Default")
      (node (ref "IC6") (pin "12") (pinfunction "+IN_12") (pintype "input"))
      (node (ref "R10") (pin "2") (pinfunction "2_2") (pintype "passive"))
      (node (ref "R9") (pin "2") (pinfunction "2_2") (pintype "passive"))
    )
    (net (code "39") (name "Net-(IC6D--IN)") (class "Default")
      (node (ref "IC6") (pin "13") (pinfunction "-IN_13") (pintype "input"))
      (node (ref "R11") (pin "2") (pinfunction "2_2") (pintype "passive"))
      (node (ref "R12") (pin "1") (pinfunction "1_1") (pintype "passive"))
    )
    (net (code "40") (name "Net-(IC6D-OUT)") (class "Default")
      (node (ref "D3") (pin "C") (pinfunction "C_C") (pintype "passive"))
      (node (ref "IC6") (pin "14") (pinfunction "OUT_14") (pintype "output"))
    )
    (net (code "41") (name "Net-(IC7-+IN)") (class "Default")
      (node (ref "IC7") (pin "1") (pinfunction "+IN_1") (pintype "input"))
      (node (ref "IC8") (pin "8") (pinfunction "OUT_8") (pintype "output"))
      (node (ref "IC8") (pin "9") (pinfunction "-IN_9") (pintype "input"))
      (node (ref "R21") (pin "2") (pinfunction "2_2") (pintype "passive"))
    )
    (net (code "42") (name "Net-(IC7--IN)") (class "Default")
      (node (ref "IC7") (pin "3") (pinfunction "-IN_3") (pintype "input"))
      (node (ref "LED2") (pin "A") (pinfunction "A_A") (pintype "passive"))
      (node (ref "R15") (pin "1") (pinfunction "1_1") (pintype "passive"))
    )
    (net (code "43") (name "Net-(IC7-OUT)") (class "Default")
      (node (ref "IC7") (pin "4") (pinfunction "OUT_4") (pintype "output"))
      (node (ref "LED2") (pin "K") (pinfunction "C_K") (pintype "passive"))
    )
    (net (code "44") (name "Net-(IC8A--IN)") (class "Default")
      (node (ref "IC8") (pin "2") (pinfunction "-IN_2") (pintype "input"))
      (node (ref "R16") (pin "2") (pinfunction "2_2") (pintype "passive"))
      (node (ref "R17") (pin "1") (pinfunction "1_1") (pintype "passive"))
    )
    (net (code "45") (name "Net-(IC8A-OUT)") (class "Default")
      (node (ref "IC8") (pin "1") (pinfunction "OUT_1") (pintype "output"))
      (node (ref "R16") (pin "1") (pinfunction "1_1") (pintype "passive"))
      (node (ref "R18") (pin "2") (pinfunction "2_2") (pintype "passive"))
    )
    (net (code "46") (name "Net-(IC8B-+IN)") (class "Default")
      (node (ref "IC8") (pin "5") (pinfunction "+IN_5") (pintype "input"))
      (node (ref "J5") (pin "P3") (pinfunction "3_P3") (pintype "passive"))
      (node (ref "R19") (pin "1") (pinfunction "1_1") (pintype "passive"))
    )
    (net (code "47") (name "Net-(IC8B--IN)") (class "Default")
      (node (ref "IC8") (pin "6") (pinfunction "-IN_6") (pintype "input"))
      (node (ref "IC8") (pin "7") (pinfunction "OUT_7") (pintype "output"))
      (node (ref "Q7") (pin "1") (pinfunction "D_1") (pintype "passive"))
      (node (ref "R20") (pin "2") (pinfunction "2_2") (pintype "passive"))
    )
    (net (code "48") (name "Net-(IC8C-+IN)") (class "Default")
      (node (ref "C19") (pin "1") (pinfunction "1_1") (pintype "passive"))
      (node (ref "IC8") (pin "10") (pinfunction "+IN_10") (pintype "input"))
      (node (ref "Q7") (pin "2") (pinfunction "S_2") (pintype "passive"))
    )
    (net (code "49") (name "Net-(IC8D-+IN)") (class "Default")
      (node (ref "IC8") (pin "12") (pinfunction "+IN_12") (pintype "input"))
      (node (ref "R23") (pin "2") (pinfunction "2_2") (pintype "passive"))
      (node (ref "R38") (pin "2") (pinfunction "2_2") (pintype "passive"))
    )
    (net (code "50") (name "Net-(IC8D--IN)") (class "Default")
      (node (ref "IC8") (pin "13") (pinfunction "-IN_13") (pintype "input"))
      (node (ref "R39") (pin "2") (pinfunction "2_2") (pintype "passive"))
      (node (ref "R40") (pin "1") (pinfunction "1_1") (pintype "passive"))
    )
    (net (code "51") (name "Net-(IC8D-OUT)") (class "Default")
      (node (ref "D5") (pin "C") (pinfunction "C_C") (pintype "passive"))
      (node (ref "IC8") (pin "14") (pinfunction "OUT_14") (pintype "output"))
    )
    (net (code "52") (name "Net-(J1-2)") (class "Default")
      (node (ref "J1") (pin "P2") (pinfunction "2_P2") (pintype "passive"))
      (node (ref "J3") (pin "P3") (pinfunction "3_P3") (pintype "passive"))
      (node (ref "R4") (pin "1") (pinfunction "1_1") (pintype "passive"))
    )
    (net (code "53") (name "Net-(J4-3)") (class "Default")
      (node (ref "J4") (pin "P3") (pinfunction "3_P3") (pintype "passive"))
      (node (ref "R7") (pin "1") (pinfunction "1_1") (pintype "passive"))
    )
    (net (code "54") (name "Net-(J5-2)") (class "Default")
      (node (ref "J5") (pin "P2") (pinfunction "2_P2") (pintype "passive"))
      (node (ref "J7") (pin "P3") (pinfunction "3_P3") (pintype "passive"))
      (node (ref "R18") (pin "1") (pinfunction "1_1") (pintype "passive"))
    )
    (net (code "55") (name "Net-(J6-3)") (class "Default")
      (node (ref "C20") (pin "1") (pinfunction "1_1") (pintype "passive"))
      (node (ref "J6") (pin "P3") (pinfunction "3_P3") (pintype "passive"))
      (node (ref "R22") (pin "2") (pinfunction "2_2") (pintype "passive"))
    )
    (net (code "56") (name "Net-(J8-3)") (class "Default")
      (node (ref "J8") (pin "P3") (pinfunction "3_P3") (pintype "passive"))
      (node (ref "R21") (pin "1") (pinfunction "1_1") (pintype "passive"))
    )
    (net (code "57") (name "Net-(J10-3)") (class "Default")
      (node (ref "C12") (pin "1") (pinfunction "1_1") (pintype "passive"))
      (node (ref "J10") (pin "P3") (pinfunction "3_P3") (pintype "passive"))
      (node (ref "R36") (pin "2") (pinfunction "2_2") (pintype "passive"))
    )
    (net (code "58") (name "Net-(J11-3)") (class "Default")
      (node (ref "J11") (pin "P3") (pinfunction "3_P3") (pintype "passive"))
      (node (ref "J9") (pin "P2") (pinfunction "2_P2") (pintype "passive"))
      (node (ref "R34") (pin "1") (pinfunction "1_1") (pintype "passive"))
    )
    (net (code "59") (name "Net-(J12-3)") (class "Default")
      (node (ref "J12") (pin "P3") (pinfunction "3_P3") (pintype "passive"))
      (node (ref "R35") (pin "1") (pinfunction "1_1") (pintype "passive"))
    )
    (net (code "60") (name "Net-(Q1-PadB)") (class "Default")
      (node (ref "Q1") (pin "B") (pinfunction "B_B") (pintype "passive"))
      (node (ref "Q2") (pin "B") (pinfunction "B_B") (pintype "passive"))
    )
    (net (code "61") (name "Net-(Q3-G)") (class "Default")
      (node (ref "D11") (pin "A") (pinfunction "A_A") (pintype "passive"))
      (node (ref "Q3") (pin "3") (pinfunction "G_3") (pintype "passive"))
      (node (ref "R32") (pin "1") (pinfunction "1_1") (pintype "passive"))
    )
    (net (code "62") (name "Net-(Q4-G)") (class "Default")
      (node (ref "D3") (pin "A") (pinfunction "A_A") (pintype "passive"))
      (node (ref "Q4") (pin "3") (pinfunction "G_3") (pintype "passive"))
      (node (ref "R6") (pin "1") (pinfunction "1_1") (pintype "passive"))
    )
    (net (code "63") (name "Net-(Q5-PadB)") (class "Default")
      (node (ref "Q5") (pin "B") (pinfunction "B_B") (pintype "passive"))
      (node (ref "Q6") (pin "B") (pinfunction "B_B") (pintype "passive"))
    )
    (net (code "64") (name "Net-(Q7-G)") (class "Default")
      (node (ref "D5") (pin "A") (pinfunction "A_A") (pintype "passive"))
      (node (ref "Q7") (pin "3") (pinfunction "G_3") (pintype "passive"))
      (node (ref "R20") (pin "1") (pinfunction "1_1") (pintype "passive"))
    )
    (net (code "65") (name "Net-(Q8-PadB)") (class "Default")
      (node (ref "Q8") (pin "B") (pinfunction "B_B") (pintype "passive"))
      (node (ref "Q9") (pin "B") (pinfunction "B_B") (pintype "passive"))
    )
    (net (code "66") (name "VCC") (class "Default")
      (node (ref "C2") (pin "1") (pinfunction "1_1") (pintype "passive"))
      (node (ref "C22") (pin "1") (pinfunction "1_1") (pintype "passive"))
      (node (ref "C24") (pin "1") (pinfunction "1_1") (pintype "passive"))
      (node (ref "C3") (pin "1") (pinfunction "1_1") (pintype "passive"))
      (node (ref "C5") (pin "1") (pinfunction "1_1") (pintype "passive"))
      (node (ref "C7") (pin "1") (pinfunction "1_1") (pintype "passive"))
      (node (ref "C9") (pin "1") (pinfunction "1_1") (pintype "passive"))
      (node (ref "IC2") (pin "5") (pinfunction "V+_5") (pintype "power_in"))
      (node (ref "IC4") (pin "4") (pinfunction "V+_4") (pintype "power_in"))
      (node (ref "IC5") (pin "5") (pinfunction "V+_5") (pintype "power_in"))
      (node (ref "IC6") (pin "4") (pinfunction "V+_4") (pintype "power_in"))
      (node (ref "IC7") (pin "5") (pinfunction "V+_5") (pintype "power_in"))
      (node (ref "IC8") (pin "4") (pinfunction "V+_4") (pintype "power_in"))
      (node (ref "L2") (pin "1") (pinfunction "1_1") (pintype "passive"))
      (node (ref "R12") (pin "2") (pinfunction "2_2") (pintype "passive"))
      (node (ref "R13") (pin "1") (pinfunction "1_1") (pintype "passive"))
      (node (ref "R14") (pin "2") (pinfunction "2_2") (pintype "passive"))
      (node (ref "R24") (pin "2") (pinfunction "2_2") (pintype "passive"))
      (node (ref "R25") (pin "2") (pinfunction "2_2") (pintype "passive"))
      (node (ref "R33") (pin "1") (pinfunction "1_1") (pintype "passive"))
      (node (ref "R40") (pin "2") (pinfunction "2_2") (pintype "passive"))
      (node (ref "R41") (pin "1") (pinfunction "1_1") (pintype "passive"))
      (node (ref "R42") (pin "2") (pinfunction "2_2") (pintype "passive"))
    )
    (net (code "67") (name "VEE") (class "Default")
      (node (ref "C1") (pin "2") (pinfunction "2_2") (pintype "passive"))
      (node (ref "C23") (pin "2") (pinfunction "2_2") (pintype "passive"))
      (node (ref "C25") (pin "2") (pinfunction "2_2") (pintype "passive"))
      (node (ref "C4") (pin "2") (pinfunction "2_2") (pintype "passive"))
      (node (ref "C6") (pin "2") (pinfunction "2_2") (pintype "passive"))
      (node (ref "C8") (pin "2") (pinfunction "2_2") (pintype "passive"))
      (node (ref "IC2") (pin "2") (pinfunction "V-_2") (pintype "power_in"))
      (node (ref "IC4") (pin "11") (pinfunction "V-_11") (pintype "power_in"))
      (node (ref "IC5") (pin "2") (pinfunction "V-_2") (pintype "power_in"))
      (node (ref "IC6") (pin "11") (pinfunction "V-_11") (pintype "power_in"))
      (node (ref "IC7") (pin "2") (pinfunction "V-_2") (pintype "power_in"))
      (node (ref "IC8") (pin "11") (pinfunction "V-_11") (pintype "power_in"))
      (node (ref "L1") (pin "1") (pinfunction "1_1") (pintype "passive"))
    )
    (net (code "68") (name "unconnected-(J3-2-PadP2)") (class "Default")
      (node (ref "J3") (pin "P2") (pinfunction "2_P2") (pintype "passive"))
    )
    (net (code "69") (name "unconnected-(J4-2-PadP2)") (class "Default")
      (node (ref "J4") (pin "P2") (pinfunction "2_P2") (pintype "passive"))
    )
    (net (code "70") (name "unconnected-(J7-2-PadP2)") (class "Default")
      (node (ref "J7") (pin "P2") (pinfunction "2_P2") (pintype "passive"))
    )
    (net (code "71") (name "unconnected-(J8-2-PadP2)") (class "Default")
      (node (ref "J8") (pin "P2") (pinfunction "2_P2") (pintype "passive"))
    )
    (net (code "72") (name "unconnected-(J11-2-PadP2)") (class "Default")
      (node (ref "J11") (pin "P2") (pinfunction "2_P2") (pintype "passive"))
    )
    (net (code "73") (name "unconnected-(J12-2-PadP2)") (class "Default")
      (node (ref "J12") (pin "P2") (pinfunction "2_P2") (pintype "passive"))
    )
    (net (code "74") (name "unconnected-(Q2-PadC)") (class "Default")
      (node (ref "Q2") (pin "C") (pinfunction "C_C") (pintype "passive"))
    )
    (net (code "75") (name "unconnected-(Q5-PadC)") (class "Default")
      (node (ref "Q5") (pin "C") (pinfunction "C_C") (pintype "passive"))
    )
    (net (code "76") (name "unconnected-(Q8-PadC)") (class "Default")
      (node (ref "Q8") (pin "C") (pinfunction "C_C") (pintype "passive"))
    )
  )
)
